# relay-set-d-decode.net
KiCad netlist of a schematic drawn in EAGLE
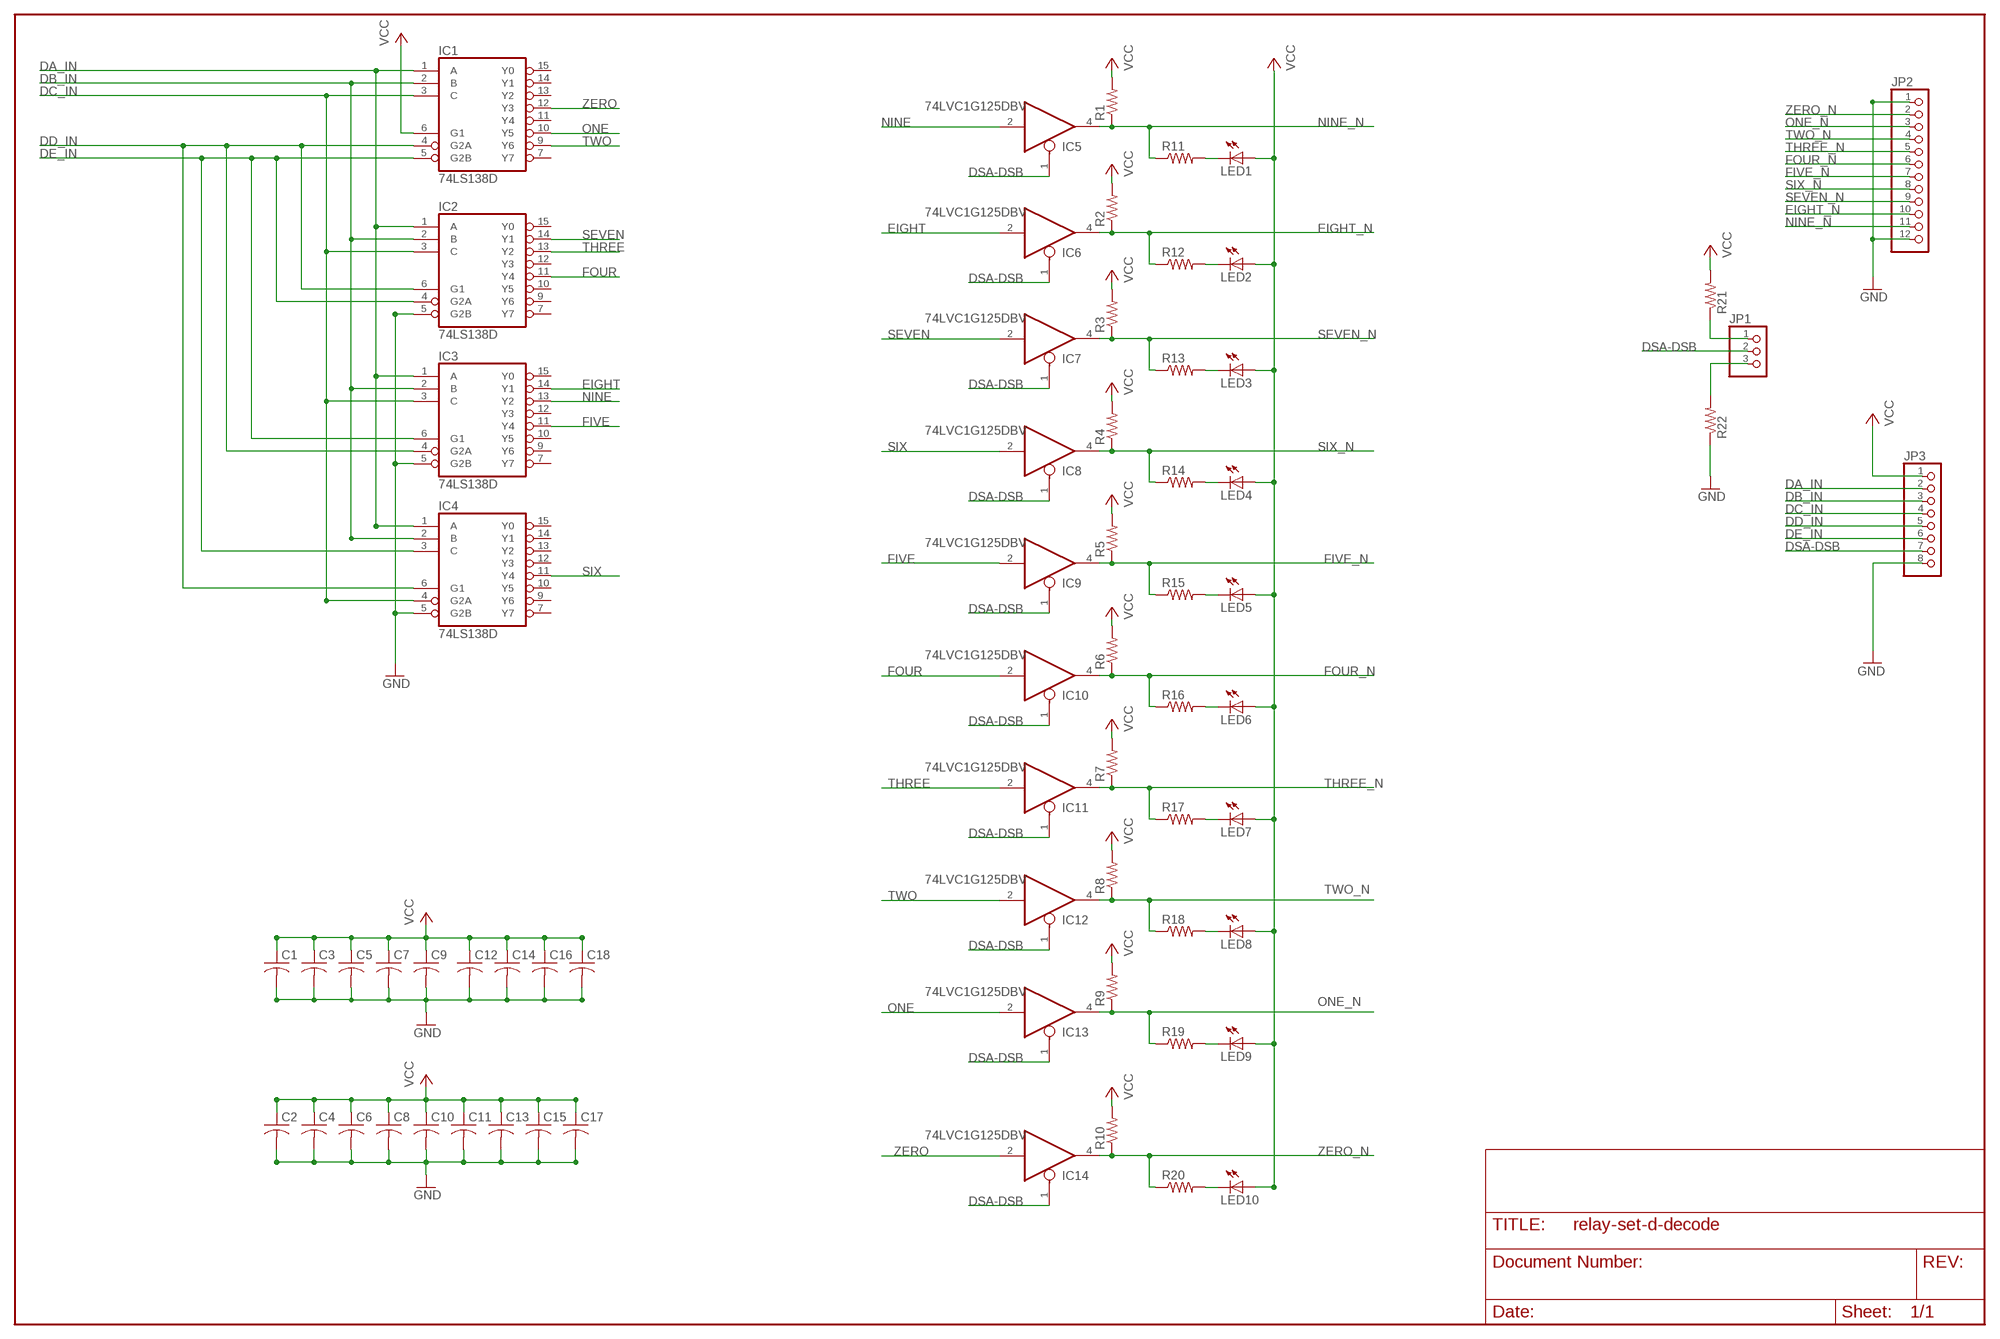
[diagram p0: schematic, sheet 1]

(export (version "E")
  (design (tool "Eeschema 10.0.6"))
  (components
    (comp (ref "C1")
      (value "C-USC0603")
      (footprint "eagle-import:C0603")
      (libsource (lib "eagle-import") (part "C-USC0603"))
    )
    (comp (ref "C2")
      (value "C-USC0603")
      (footprint "eagle-import:C0603")
      (libsource (lib "eagle-import") (part "C-USC0603"))
    )
    (comp (ref "C3")
      (value "C-USC0603")
      (footprint "eagle-import:C0603")
      (libsource (lib "eagle-import") (part "C-USC0603"))
    )
    (comp (ref "C4")
      (value "C-USC0603")
      (footprint "eagle-import:C0603")
      (libsource (lib "eagle-import") (part "C-USC0603"))
    )
    (comp (ref "C5")
      (value "C-USC0805")
      (footprint "eagle-import:C0805")
      (libsource (lib "eagle-import") (part "C-USC0805"))
    )
    (comp (ref "C6")
      (value "C-USC0603")
      (footprint "eagle-import:C0603")
      (libsource (lib "eagle-import") (part "C-USC0603"))
    )
    (comp (ref "C7")
      (value "C-USC0805")
      (footprint "eagle-import:C0805")
      (libsource (lib "eagle-import") (part "C-USC0805"))
    )
    (comp (ref "C8")
      (value "C-USC0603")
      (footprint "eagle-import:C0603")
      (libsource (lib "eagle-import") (part "C-USC0603"))
    )
    (comp (ref "C9")
      (value "C-USC0805")
      (footprint "eagle-import:C0805")
      (libsource (lib "eagle-import") (part "C-USC0805"))
    )
    (comp (ref "C10")
      (value "C-USC0603")
      (footprint "eagle-import:C0603")
      (libsource (lib "eagle-import") (part "C-USC0603"))
    )
    (comp (ref "C11")
      (value "C-USC0603")
      (footprint "eagle-import:C0603")
      (libsource (lib "eagle-import") (part "C-USC0603"))
    )
    (comp (ref "C12")
      (value "C-USC0603")
      (footprint "eagle-import:C0603")
      (libsource (lib "eagle-import") (part "C-USC0603"))
    )
    (comp (ref "C13")
      (value "C-USC0603")
      (footprint "eagle-import:C0603")
      (libsource (lib "eagle-import") (part "C-USC0603"))
    )
    (comp (ref "C14")
      (value "C-USC0603")
      (footprint "eagle-import:C0603")
      (libsource (lib "eagle-import") (part "C-USC0603"))
    )
    (comp (ref "C15")
      (value "C-USC0603")
      (footprint "eagle-import:C0603")
      (libsource (lib "eagle-import") (part "C-USC0603"))
    )
    (comp (ref "C16")
      (value "C-USC0603")
      (footprint "eagle-import:C0603")
      (libsource (lib "eagle-import") (part "C-USC0603"))
    )
    (comp (ref "C17")
      (value "C-USC0603")
      (footprint "eagle-import:C0603")
      (libsource (lib "eagle-import") (part "C-USC0603"))
    )
    (comp (ref "C18")
      (value "C-USC0603")
      (footprint "eagle-import:C0603")
      (libsource (lib "eagle-import") (part "C-USC0603"))
    )
    (comp (ref "IC1")
      (value "74LS138D")
      (footprint "eagle-import:SO16")
      (libsource (lib "eagle-import") (part "74138DLS"))
    )
    (comp (ref "IC2")
      (value "74LS138D")
      (footprint "eagle-import:SO16")
      (libsource (lib "eagle-import") (part "74138DLS"))
    )
    (comp (ref "IC3")
      (value "74LS138D")
      (footprint "eagle-import:SO16")
      (libsource (lib "eagle-import") (part "74138DLS"))
    )
    (comp (ref "IC4")
      (value "74LS138D")
      (footprint "eagle-import:SO16")
      (libsource (lib "eagle-import") (part "74138DLS"))
    )
    (comp (ref "IC5")
      (value "74LVC1G125DBV")
      (footprint "eagle-import:SOT23-5")
      (libsource (lib "eagle-import") (part "741G125DBVLVC"))
    )
    (comp (ref "IC6")
      (value "74LVC1G125DBV")
      (footprint "eagle-import:SOT23-5")
      (libsource (lib "eagle-import") (part "741G125DBVLVC"))
    )
    (comp (ref "IC7")
      (value "74LVC1G125DBV")
      (footprint "eagle-import:SOT23-5")
      (libsource (lib "eagle-import") (part "741G125DBVLVC"))
    )
    (comp (ref "IC8")
      (value "74LVC1G125DBV")
      (footprint "eagle-import:SOT23-5")
      (libsource (lib "eagle-import") (part "741G125DBVLVC"))
    )
    (comp (ref "IC9")
      (value "74LVC1G125DBV")
      (footprint "eagle-import:SOT23-5")
      (libsource (lib "eagle-import") (part "741G125DBVLVC"))
    )
    (comp (ref "IC10")
      (value "74LVC1G125DBV")
      (footprint "eagle-import:SOT23-5")
      (libsource (lib "eagle-import") (part "741G125DBVLVC"))
    )
    (comp (ref "IC11")
      (value "74LVC1G125DBV")
      (footprint "eagle-import:SOT23-5")
      (libsource (lib "eagle-import") (part "741G125DBVLVC"))
    )
    (comp (ref "IC12")
      (value "74LVC1G125DBV")
      (footprint "eagle-import:SOT23-5")
      (libsource (lib "eagle-import") (part "741G125DBVLVC"))
    )
    (comp (ref "IC13")
      (value "74LVC1G125DBV")
      (footprint "eagle-import:SOT23-5")
      (libsource (lib "eagle-import") (part "741G125DBVLVC"))
    )
    (comp (ref "IC14")
      (value "74LVC1G125DBV")
      (footprint "eagle-import:SOT23-5")
      (libsource (lib "eagle-import") (part "741G125DBVLVC"))
    )
    (comp (ref "JP1")
      (value "PINHD-1X3")
      (footprint "eagle-import:1X03")
      (libsource (lib "eagle-import") (part "PINHD-1X3"))
    )
    (comp (ref "JP2")
      (value "PINHD-1X12")
      (footprint "eagle-import:1X12")
      (libsource (lib "eagle-import") (part "PINHD-1X12"))
    )
    (comp (ref "JP3")
      (value "PINHD-1X8")
      (footprint "eagle-import:1X08")
      (libsource (lib "eagle-import") (part "PINHD-1X8"))
    )
    (comp (ref "LED1")
      (value "LEDCHIP-LED0805")
      (footprint "eagle-import:CHIP-LED0805")
      (libsource (lib "eagle-import") (part "LEDCHIP-LED0805"))
    )
    (comp (ref "LED2")
      (value "LEDCHIP-LED0805")
      (footprint "eagle-import:CHIP-LED0805")
      (libsource (lib "eagle-import") (part "LEDCHIP-LED0805"))
    )
    (comp (ref "LED3")
      (value "LEDCHIP-LED0805")
      (footprint "eagle-import:CHIP-LED0805")
      (libsource (lib "eagle-import") (part "LEDCHIP-LED0805"))
    )
    (comp (ref "LED4")
      (value "LEDCHIP-LED0805")
      (footprint "eagle-import:CHIP-LED0805")
      (libsource (lib "eagle-import") (part "LEDCHIP-LED0805"))
    )
    (comp (ref "LED5")
      (value "LEDCHIP-LED0805")
      (footprint "eagle-import:CHIP-LED0805")
      (libsource (lib "eagle-import") (part "LEDCHIP-LED0805"))
    )
    (comp (ref "LED6")
      (value "LEDCHIP-LED0805")
      (footprint "eagle-import:CHIP-LED0805")
      (libsource (lib "eagle-import") (part "LEDCHIP-LED0805"))
    )
    (comp (ref "LED7")
      (value "LEDCHIP-LED0805")
      (footprint "eagle-import:CHIP-LED0805")
      (libsource (lib "eagle-import") (part "LEDCHIP-LED0805"))
    )
    (comp (ref "LED8")
      (value "LEDCHIP-LED0805")
      (footprint "eagle-import:CHIP-LED0805")
      (libsource (lib "eagle-import") (part "LEDCHIP-LED0805"))
    )
    (comp (ref "LED9")
      (value "LEDCHIP-LED0805")
      (footprint "eagle-import:CHIP-LED0805")
      (libsource (lib "eagle-import") (part "LEDCHIP-LED0805"))
    )
    (comp (ref "LED10")
      (value "LEDCHIP-LED0805")
      (footprint "eagle-import:CHIP-LED0805")
      (libsource (lib "eagle-import") (part "LEDCHIP-LED0805"))
    )
    (comp (ref "R1")
      (value "R-US_R0805")
      (footprint "eagle-import:R0805")
      (libsource (lib "eagle-import") (part "R-US_R0805"))
    )
    (comp (ref "R2")
      (value "R-US_R0805")
      (footprint "eagle-import:R0805")
      (libsource (lib "eagle-import") (part "R-US_R0805"))
    )
    (comp (ref "R3")
      (value "R-US_R0805")
      (footprint "eagle-import:R0805")
      (libsource (lib "eagle-import") (part "R-US_R0805"))
    )
    (comp (ref "R4")
      (value "R-US_R0805")
      (footprint "eagle-import:R0805")
      (libsource (lib "eagle-import") (part "R-US_R0805"))
    )
    (comp (ref "R5")
      (value "R-US_R0805")
      (footprint "eagle-import:R0805")
      (libsource (lib "eagle-import") (part "R-US_R0805"))
    )
    (comp (ref "R6")
      (value "R-US_R0805")
      (footprint "eagle-import:R0805")
      (libsource (lib "eagle-import") (part "R-US_R0805"))
    )
    (comp (ref "R7")
      (value "R-US_R0805")
      (footprint "eagle-import:R0805")
      (libsource (lib "eagle-import") (part "R-US_R0805"))
    )
    (comp (ref "R8")
      (value "R-US_R0805")
      (footprint "eagle-import:R0805")
      (libsource (lib "eagle-import") (part "R-US_R0805"))
    )
    (comp (ref "R9")
      (value "R-US_R0805")
      (footprint "eagle-import:R0805")
      (libsource (lib "eagle-import") (part "R-US_R0805"))
    )
    (comp (ref "R10")
      (value "R-US_R0805")
      (footprint "eagle-import:R0805")
      (libsource (lib "eagle-import") (part "R-US_R0805"))
    )
    (comp (ref "R11")
      (value "R-US_R0805")
      (footprint "eagle-import:R0805")
      (libsource (lib "eagle-import") (part "R-US_R0805"))
    )
    (comp (ref "R12")
      (value "R-US_R0805")
      (footprint "eagle-import:R0805")
      (libsource (lib "eagle-import") (part "R-US_R0805"))
    )
    (comp (ref "R13")
      (value "R-US_R0805")
      (footprint "eagle-import:R0805")
      (libsource (lib "eagle-import") (part "R-US_R0805"))
    )
    (comp (ref "R14")
      (value "R-US_R0805")
      (footprint "eagle-import:R0805")
      (libsource (lib "eagle-import") (part "R-US_R0805"))
    )
    (comp (ref "R15")
      (value "R-US_R0805")
      (footprint "eagle-import:R0805")
      (libsource (lib "eagle-import") (part "R-US_R0805"))
    )
    (comp (ref "R16")
      (value "R-US_R0805")
      (footprint "eagle-import:R0805")
      (libsource (lib "eagle-import") (part "R-US_R0805"))
    )
    (comp (ref "R17")
      (value "R-US_R0805")
      (footprint "eagle-import:R0805")
      (libsource (lib "eagle-import") (part "R-US_R0805"))
    )
    (comp (ref "R18")
      (value "R-US_R0805")
      (footprint "eagle-import:R0805")
      (libsource (lib "eagle-import") (part "R-US_R0805"))
    )
    (comp (ref "R19")
      (value "R-US_R0805")
      (footprint "eagle-import:R0805")
      (libsource (lib "eagle-import") (part "R-US_R0805"))
    )
    (comp (ref "R20")
      (value "R-US_R0805")
      (footprint "eagle-import:R0805")
      (libsource (lib "eagle-import") (part "R-US_R0805"))
    )
    (comp (ref "R21")
      (value "R-US_R0805")
      (footprint "eagle-import:R0805")
      (libsource (lib "eagle-import") (part "R-US_R0805"))
    )
    (comp (ref "R22")
      (value "R-US_R0805")
      (footprint "eagle-import:R0805")
      (libsource (lib "eagle-import") (part "R-US_R0805"))
    )
  )
  (nets
    (net (code "1") (name "/DA_IN") (class "Default")
      (node (ref "IC1") (pin "1") (pinfunction "A_1") (pintype "input"))
      (node (ref "IC2") (pin "1") (pinfunction "A_1") (pintype "input"))
      (node (ref "IC3") (pin "1") (pinfunction "A_1") (pintype "input"))
      (node (ref "IC4") (pin "1") (pinfunction "A_1") (pintype "input"))
      (node (ref "JP3") (pin "2") (pinfunction "2_2") (pintype "passive"))
    )
    (net (code "2") (name "/DB_IN") (class "Default")
      (node (ref "IC1") (pin "2") (pinfunction "B_2") (pintype "input"))
      (node (ref "IC2") (pin "2") (pinfunction "B_2") (pintype "input"))
      (node (ref "IC3") (pin "2") (pinfunction "B_2") (pintype "input"))
      (node (ref "IC4") (pin "2") (pinfunction "B_2") (pintype "input"))
      (node (ref "JP3") (pin "3") (pinfunction "3_3") (pintype "passive"))
    )
    (net (code "3") (name "/DC_IN") (class "Default")
      (node (ref "IC1") (pin "3") (pinfunction "C_3") (pintype "input"))
      (node (ref "IC2") (pin "3") (pinfunction "C_3") (pintype "input"))
      (node (ref "IC3") (pin "3") (pinfunction "C_3") (pintype "input"))
      (node (ref "IC4") (pin "4") (pinfunction "G2A_4") (pintype "input"))
      (node (ref "JP3") (pin "4") (pinfunction "4_4") (pintype "passive"))
    )
    (net (code "4") (name "/DD_IN") (class "Default")
      (node (ref "IC1") (pin "4") (pinfunction "G2A_4") (pintype "input"))
      (node (ref "IC2") (pin "6") (pinfunction "G1_6") (pintype "input"))
      (node (ref "IC3") (pin "4") (pinfunction "G2A_4") (pintype "input"))
      (node (ref "IC4") (pin "6") (pinfunction "G1_6") (pintype "input"))
      (node (ref "JP3") (pin "5") (pinfunction "5_5") (pintype "passive"))
    )
    (net (code "5") (name "/DE_IN") (class "Default")
      (node (ref "IC1") (pin "5") (pinfunction "G2B_5") (pintype "input"))
      (node (ref "IC2") (pin "4") (pinfunction "G2A_4") (pintype "input"))
      (node (ref "IC3") (pin "6") (pinfunction "G1_6") (pintype "input"))
      (node (ref "IC4") (pin "3") (pinfunction "C_3") (pintype "input"))
      (node (ref "JP3") (pin "6") (pinfunction "6_6") (pintype "passive"))
    )
    (net (code "6") (name "/DSA-DSB") (class "Default")
      (node (ref "IC10") (pin "1") (pinfunction "OE_1") (pintype "input"))
      (node (ref "IC11") (pin "1") (pinfunction "OE_1") (pintype "input"))
      (node (ref "IC12") (pin "1") (pinfunction "OE_1") (pintype "input"))
      (node (ref "IC13") (pin "1") (pinfunction "OE_1") (pintype "input"))
      (node (ref "IC14") (pin "1") (pinfunction "OE_1") (pintype "input"))
      (node (ref "IC5") (pin "1") (pinfunction "OE_1") (pintype "input"))
      (node (ref "IC6") (pin "1") (pinfunction "OE_1") (pintype "input"))
      (node (ref "IC7") (pin "1") (pinfunction "OE_1") (pintype "input"))
      (node (ref "IC8") (pin "1") (pinfunction "OE_1") (pintype "input"))
      (node (ref "IC9") (pin "1") (pinfunction "OE_1") (pintype "input"))
      (node (ref "JP1") (pin "2") (pinfunction "2_2") (pintype "passive"))
      (node (ref "JP3") (pin "7") (pinfunction "7_7") (pintype "passive"))
    )
    (net (code "7") (name "/EIGHT") (class "Default")
      (node (ref "IC3") (pin "14") (pinfunction "Y1_14") (pintype "output"))
      (node (ref "IC6") (pin "2") (pinfunction "I_2") (pintype "input"))
    )
    (net (code "8") (name "/EIGHT_N") (class "Default")
      (node (ref "IC6") (pin "4") (pinfunction "O_4") (pintype "tri_state"))
      (node (ref "JP2") (pin "10") (pinfunction "10_10") (pintype "passive"))
      (node (ref "R12") (pin "1") (pinfunction "1_1") (pintype "passive"))
      (node (ref "R2") (pin "1") (pinfunction "1_1") (pintype "passive"))
    )
    (net (code "9") (name "/FIVE") (class "Default")
      (node (ref "IC3") (pin "11") (pinfunction "Y4_11") (pintype "output"))
      (node (ref "IC9") (pin "2") (pinfunction "I_2") (pintype "input"))
    )
    (net (code "10") (name "/FIVE_N") (class "Default")
      (node (ref "IC9") (pin "4") (pinfunction "O_4") (pintype "tri_state"))
      (node (ref "JP2") (pin "7") (pinfunction "7_7") (pintype "passive"))
      (node (ref "R15") (pin "1") (pinfunction "1_1") (pintype "passive"))
      (node (ref "R5") (pin "1") (pinfunction "1_1") (pintype "passive"))
    )
    (net (code "11") (name "/FOUR") (class "Default")
      (node (ref "IC10") (pin "2") (pinfunction "I_2") (pintype "input"))
      (node (ref "IC2") (pin "11") (pinfunction "Y4_11") (pintype "output"))
    )
    (net (code "12") (name "/FOUR_N") (class "Default")
      (node (ref "IC10") (pin "4") (pinfunction "O_4") (pintype "tri_state"))
      (node (ref "JP2") (pin "6") (pinfunction "6_6") (pintype "passive"))
      (node (ref "R16") (pin "1") (pinfunction "1_1") (pintype "passive"))
      (node (ref "R6") (pin "1") (pinfunction "1_1") (pintype "passive"))
    )
    (net (code "13") (name "/NINE") (class "Default")
      (node (ref "IC3") (pin "13") (pinfunction "Y2_13") (pintype "output"))
      (node (ref "IC5") (pin "2") (pinfunction "I_2") (pintype "input"))
    )
    (net (code "14") (name "/NINE_N") (class "Default")
      (node (ref "IC5") (pin "4") (pinfunction "O_4") (pintype "tri_state"))
      (node (ref "JP2") (pin "11") (pinfunction "11_11") (pintype "passive"))
      (node (ref "R1") (pin "1") (pinfunction "1_1") (pintype "passive"))
      (node (ref "R11") (pin "1") (pinfunction "1_1") (pintype "passive"))
    )
    (net (code "15") (name "/ONE") (class "Default")
      (node (ref "IC1") (pin "10") (pinfunction "Y5_10") (pintype "output"))
      (node (ref "IC13") (pin "2") (pinfunction "I_2") (pintype "input"))
    )
    (net (code "16") (name "/ONE_N") (class "Default")
      (node (ref "IC13") (pin "4") (pinfunction "O_4") (pintype "tri_state"))
      (node (ref "JP2") (pin "3") (pinfunction "3_3") (pintype "passive"))
      (node (ref "R19") (pin "1") (pinfunction "1_1") (pintype "passive"))
      (node (ref "R9") (pin "1") (pinfunction "1_1") (pintype "passive"))
    )
    (net (code "17") (name "/SEVEN") (class "Default")
      (node (ref "IC2") (pin "14") (pinfunction "Y1_14") (pintype "output"))
      (node (ref "IC7") (pin "2") (pinfunction "I_2") (pintype "input"))
    )
    (net (code "18") (name "/SEVEN_N") (class "Default")
      (node (ref "IC7") (pin "4") (pinfunction "O_4") (pintype "tri_state"))
      (node (ref "JP2") (pin "9") (pinfunction "9_9") (pintype "passive"))
      (node (ref "R13") (pin "1") (pinfunction "1_1") (pintype "passive"))
      (node (ref "R3") (pin "1") (pinfunction "1_1") (pintype "passive"))
    )
    (net (code "19") (name "/SIX") (class "Default")
      (node (ref "IC4") (pin "11") (pinfunction "Y4_11") (pintype "output"))
      (node (ref "IC8") (pin "2") (pinfunction "I_2") (pintype "input"))
    )
    (net (code "20") (name "/SIX_N") (class "Default")
      (node (ref "IC8") (pin "4") (pinfunction "O_4") (pintype "tri_state"))
      (node (ref "JP2") (pin "8") (pinfunction "8_8") (pintype "passive"))
      (node (ref "R14") (pin "1") (pinfunction "1_1") (pintype "passive"))
      (node (ref "R4") (pin "1") (pinfunction "1_1") (pintype "passive"))
    )
    (net (code "21") (name "/THREE") (class "Default")
      (node (ref "IC11") (pin "2") (pinfunction "I_2") (pintype "input"))
      (node (ref "IC2") (pin "13") (pinfunction "Y2_13") (pintype "output"))
    )
    (net (code "22") (name "/THREE_N") (class "Default")
      (node (ref "IC11") (pin "4") (pinfunction "O_4") (pintype "tri_state"))
      (node (ref "JP2") (pin "5") (pinfunction "5_5") (pintype "passive"))
      (node (ref "R17") (pin "1") (pinfunction "1_1") (pintype "passive"))
      (node (ref "R7") (pin "1") (pinfunction "1_1") (pintype "passive"))
    )
    (net (code "23") (name "/TWO") (class "Default")
      (node (ref "IC1") (pin "9") (pinfunction "Y6_9") (pintype "output"))
      (node (ref "IC12") (pin "2") (pinfunction "I_2") (pintype "input"))
    )
    (net (code "24") (name "/TWO_N") (class "Default")
      (node (ref "IC12") (pin "4") (pinfunction "O_4") (pintype "tri_state"))
      (node (ref "JP2") (pin "4") (pinfunction "4_4") (pintype "passive"))
      (node (ref "R18") (pin "1") (pinfunction "1_1") (pintype "passive"))
      (node (ref "R8") (pin "1") (pinfunction "1_1") (pintype "passive"))
    )
    (net (code "25") (name "/ZERO") (class "Default")
      (node (ref "IC1") (pin "12") (pinfunction "Y3_12") (pintype "output"))
      (node (ref "IC14") (pin "2") (pinfunction "I_2") (pintype "input"))
    )
    (net (code "26") (name "/ZERO_N") (class "Default")
      (node (ref "IC14") (pin "4") (pinfunction "O_4") (pintype "tri_state"))
      (node (ref "JP2") (pin "2") (pinfunction "2_2") (pintype "passive"))
      (node (ref "R10") (pin "1") (pinfunction "1_1") (pintype "passive"))
      (node (ref "R20") (pin "1") (pinfunction "1_1") (pintype "passive"))
    )
    (net (code "27") (name "GND") (class "Default")
      (node (ref "C1") (pin "2") (pinfunction "2_2") (pintype "passive"))
      (node (ref "C10") (pin "2") (pinfunction "2_2") (pintype "passive"))
      (node (ref "C11") (pin "2") (pinfunction "2_2") (pintype "passive"))
      (node (ref "C12") (pin "2") (pinfunction "2_2") (pintype "passive"))
      (node (ref "C13") (pin "2") (pinfunction "2_2") (pintype "passive"))
      (node (ref "C14") (pin "2") (pinfunction "2_2") (pintype "passive"))
      (node (ref "C15") (pin "2") (pinfunction "2_2") (pintype "passive"))
      (node (ref "C16") (pin "2") (pinfunction "2_2") (pintype "passive"))
      (node (ref "C17") (pin "2") (pinfunction "2_2") (pintype "passive"))
      (node (ref "C18") (pin "2") (pinfunction "2_2") (pintype "passive"))
      (node (ref "C2") (pin "2") (pinfunction "2_2") (pintype "passive"))
      (node (ref "C3") (pin "2") (pinfunction "2_2") (pintype "passive"))
      (node (ref "C4") (pin "2") (pinfunction "2_2") (pintype "passive"))
      (node (ref "C5") (pin "2") (pinfunction "2_2") (pintype "passive"))
      (node (ref "C6") (pin "2") (pinfunction "2_2") (pintype "passive"))
      (node (ref "C7") (pin "2") (pinfunction "2_2") (pintype "passive"))
      (node (ref "C8") (pin "2") (pinfunction "2_2") (pintype "passive"))
      (node (ref "C9") (pin "2") (pinfunction "2_2") (pintype "passive"))
      (node (ref "IC2") (pin "5") (pinfunction "G2B_5") (pintype "input"))
      (node (ref "IC3") (pin "5") (pinfunction "G2B_5") (pintype "input"))
      (node (ref "IC4") (pin "5") (pinfunction "G2B_5") (pintype "input"))
      (node (ref "JP2") (pin "1") (pinfunction "1_1") (pintype "passive"))
      (node (ref "JP2") (pin "12") (pinfunction "12_12") (pintype "passive"))
      (node (ref "JP3") (pin "8") (pinfunction "8_8") (pintype "passive"))
      (node (ref "R22") (pin "1") (pinfunction "1_1") (pintype "passive"))
    )
    (net (code "28") (name "Net-(JP1-Pad1)") (class "Default")
      (node (ref "JP1") (pin "1") (pinfunction "1_1") (pintype "passive"))
      (node (ref "R21") (pin "1") (pinfunction "1_1") (pintype "passive"))
    )
    (net (code "29") (name "Net-(JP1-Pad3)") (class "Default")
      (node (ref "JP1") (pin "3") (pinfunction "3_3") (pintype "passive"))
      (node (ref "R22") (pin "2") (pinfunction "2_2") (pintype "passive"))
    )
    (net (code "30") (name "Net-(LED1-PadC)") (class "Default")
      (node (ref "LED1") (pin "C") (pinfunction "C_C") (pintype "passive"))
      (node (ref "R11") (pin "2") (pinfunction "2_2") (pintype "passive"))
    )
    (net (code "31") (name "Net-(LED2-PadC)") (class "Default")
      (node (ref "LED2") (pin "C") (pinfunction "C_C") (pintype "passive"))
      (node (ref "R12") (pin "2") (pinfunction "2_2") (pintype "passive"))
    )
    (net (code "32") (name "Net-(LED3-PadC)") (class "Default")
      (node (ref "LED3") (pin "C") (pinfunction "C_C") (pintype "passive"))
      (node (ref "R13") (pin "2") (pinfunction "2_2") (pintype "passive"))
    )
    (net (code "33") (name "Net-(LED4-PadC)") (class "Default")
      (node (ref "LED4") (pin "C") (pinfunction "C_C") (pintype "passive"))
      (node (ref "R14") (pin "2") (pinfunction "2_2") (pintype "passive"))
    )
    (net (code "34") (name "Net-(LED5-PadC)") (class "Default")
      (node (ref "LED5") (pin "C") (pinfunction "C_C") (pintype "passive"))
      (node (ref "R15") (pin "2") (pinfunction "2_2") (pintype "passive"))
    )
    (net (code "35") (name "Net-(LED6-PadC)") (class "Default")
      (node (ref "LED6") (pin "C") (pinfunction "C_C") (pintype "passive"))
      (node (ref "R16") (pin "2") (pinfunction "2_2") (pintype "passive"))
    )
    (net (code "36") (name "Net-(LED7-PadC)") (class "Default")
      (node (ref "LED7") (pin "C") (pinfunction "C_C") (pintype "passive"))
      (node (ref "R17") (pin "2") (pinfunction "2_2") (pintype "passive"))
    )
    (net (code "37") (name "Net-(LED8-PadC)") (class "Default")
      (node (ref "LED8") (pin "C") (pinfunction "C_C") (pintype "passive"))
      (node (ref "R18") (pin "2") (pinfunction "2_2") (pintype "passive"))
    )
    (net (code "38") (name "Net-(LED9-PadC)") (class "Default")
      (node (ref "LED9") (pin "C") (pinfunction "C_C") (pintype "passive"))
      (node (ref "R19") (pin "2") (pinfunction "2_2") (pintype "passive"))
    )
    (net (code "39") (name "Net-(LED10-PadC)") (class "Default")
      (node (ref "LED10") (pin "C") (pinfunction "C_C") (pintype "passive"))
      (node (ref "R20") (pin "2") (pinfunction "2_2") (pintype "passive"))
    )
    (net (code "40") (name "VCC") (class "Default")
      (node (ref "C1") (pin "1") (pinfunction "1_1") (pintype "passive"))
      (node (ref "C10") (pin "1") (pinfunction "1_1") (pintype "passive"))
      (node (ref "C11") (pin "1") (pinfunction "1_1") (pintype "passive"))
      (node (ref "C12") (pin "1") (pinfunction "1_1") (pintype "passive"))
      (node (ref "C13") (pin "1") (pinfunction "1_1") (pintype "passive"))
      (node (ref "C14") (pin "1") (pinfunction "1_1") (pintype "passive"))
      (node (ref "C15") (pin "1") (pinfunction "1_1") (pintype "passive"))
      (node (ref "C16") (pin "1") (pinfunction "1_1") (pintype "passive"))
      (node (ref "C17") (pin "1") (pinfunction "1_1") (pintype "passive"))
      (node (ref "C18") (pin "1") (pinfunction "1_1") (pintype "passive"))
      (node (ref "C2") (pin "1") (pinfunction "1_1") (pintype "passive"))
      (node (ref "C3") (pin "1") (pinfunction "1_1") (pintype "passive"))
      (node (ref "C4") (pin "1") (pinfunction "1_1") (pintype "passive"))
      (node (ref "C5") (pin "1") (pinfunction "1_1") (pintype "passive"))
      (node (ref "C6") (pin "1") (pinfunction "1_1") (pintype "passive"))
      (node (ref "C7") (pin "1") (pinfunction "1_1") (pintype "passive"))
      (node (ref "C8") (pin "1") (pinfunction "1_1") (pintype "passive"))
      (node (ref "C9") (pin "1") (pinfunction "1_1") (pintype "passive"))
      (node (ref "IC1") (pin "6") (pinfunction "G1_6") (pintype "input"))
      (node (ref "JP3") (pin "1") (pinfunction "1_1") (pintype "passive"))
      (node (ref "LED1") (pin "A") (pinfunction "A_A") (pintype "passive"))
      (node (ref "LED10") (pin "A") (pinfunction "A_A") (pintype "passive"))
      (node (ref "LED2") (pin "A") (pinfunction "A_A") (pintype "passive"))
      (node (ref "LED3") (pin "A") (pinfunction "A_A") (pintype "passive"))
      (node (ref "LED4") (pin "A") (pinfunction "A_A") (pintype "passive"))
      (node (ref "LED5") (pin "A") (pinfunction "A_A") (pintype "passive"))
      (node (ref "LED6") (pin "A") (pinfunction "A_A") (pintype "passive"))
      (node (ref "LED7") (pin "A") (pinfunction "A_A") (pintype "passive"))
      (node (ref "LED8") (pin "A") (pinfunction "A_A") (pintype "passive"))
      (node (ref "LED9") (pin "A") (pinfunction "A_A") (pintype "passive"))
      (node (ref "R1") (pin "2") (pinfunction "2_2") (pintype "passive"))
      (node (ref "R10") (pin "2") (pinfunction "2_2") (pintype "passive"))
      (node (ref "R2") (pin "2") (pinfunction "2_2") (pintype "passive"))
      (node (ref "R21") (pin "2") (pinfunction "2_2") (pintype "passive"))
      (node (ref "R3") (pin "2") (pinfunction "2_2") (pintype "passive"))
      (node (ref "R4") (pin "2") (pinfunction "2_2") (pintype "passive"))
      (node (ref "R5") (pin "2") (pinfunction "2_2") (pintype "passive"))
      (node (ref "R6") (pin "2") (pinfunction "2_2") (pintype "passive"))
      (node (ref "R7") (pin "2") (pinfunction "2_2") (pintype "passive"))
      (node (ref "R8") (pin "2") (pinfunction "2_2") (pintype "passive"))
      (node (ref "R9") (pin "2") (pinfunction "2_2") (pintype "passive"))
    )
    (net (code "41") (name "unconnected-(IC1A-Y0-Pad15)") (class "Default")
      (node (ref "IC1") (pin "15") (pinfunction "Y0_15") (pintype "output"))
    )
    (net (code "42") (name "unconnected-(IC1A-Y1-Pad14)") (class "Default")
      (node (ref "IC1") (pin "14") (pinfunction "Y1_14") (pintype "output"))
    )
    (net (code "43") (name "unconnected-(IC1A-Y2-Pad13)") (class "Default")
      (node (ref "IC1") (pin "13") (pinfunction "Y2_13") (pintype "output"))
    )
    (net (code "44") (name "unconnected-(IC1A-Y4-Pad11)") (class "Default")
      (node (ref "IC1") (pin "11") (pinfunction "Y4_11") (pintype "output"))
    )
    (net (code "45") (name "unconnected-(IC1A-Y7-Pad7)") (class "Default")
      (node (ref "IC1") (pin "7") (pinfunction "Y7_7") (pintype "output"))
    )
    (net (code "46") (name "unconnected-(IC2A-Y0-Pad15)") (class "Default")
      (node (ref "IC2") (pin "15") (pinfunction "Y0_15") (pintype "output"))
    )
    (net (code "47") (name "unconnected-(IC2A-Y3-Pad12)") (class "Default")
      (node (ref "IC2") (pin "12") (pinfunction "Y3_12") (pintype "output"))
    )
    (net (code "48") (name "unconnected-(IC2A-Y5-Pad10)") (class "Default")
      (node (ref "IC2") (pin "10") (pinfunction "Y5_10") (pintype "output"))
    )
    (net (code "49") (name "unconnected-(IC2A-Y6-Pad9)") (class "Default")
      (node (ref "IC2") (pin "9") (pinfunction "Y6_9") (pintype "output"))
    )
    (net (code "50") (name "unconnected-(IC2A-Y7-Pad7)") (class "Default")
      (node (ref "IC2") (pin "7") (pinfunction "Y7_7") (pintype "output"))
    )
    (net (code "51") (name "unconnected-(IC3A-Y0-Pad15)") (class "Default")
      (node (ref "IC3") (pin "15") (pinfunction "Y0_15") (pintype "output"))
    )
    (net (code "52") (name "unconnected-(IC3A-Y3-Pad12)") (class "Default")
      (node (ref "IC3") (pin "12") (pinfunction "Y3_12") (pintype "output"))
    )
    (net (code "53") (name "unconnected-(IC3A-Y5-Pad10)") (class "Default")
      (node (ref "IC3") (pin "10") (pinfunction "Y5_10") (pintype "output"))
    )
    (net (code "54") (name "unconnected-(IC3A-Y6-Pad9)") (class "Default")
      (node (ref "IC3") (pin "9") (pinfunction "Y6_9") (pintype "output"))
    )
    (net (code "55") (name "unconnected-(IC3A-Y7-Pad7)") (class "Default")
      (node (ref "IC3") (pin "7") (pinfunction "Y7_7") (pintype "output"))
    )
    (net (code "56") (name "unconnected-(IC4A-Y0-Pad15)") (class "Default")
      (node (ref "IC4") (pin "15") (pinfunction "Y0_15") (pintype "output"))
    )
    (net (code "57") (name "unconnected-(IC4A-Y1-Pad14)") (class "Default")
      (node (ref "IC4") (pin "14") (pinfunction "Y1_14") (pintype "output"))
    )
    (net (code "58") (name "unconnected-(IC4A-Y2-Pad13)") (class "Default")
      (node (ref "IC4") (pin "13") (pinfunction "Y2_13") (pintype "output"))
    )
    (net (code "59") (name "unconnected-(IC4A-Y3-Pad12)") (class "Default")
      (node (ref "IC4") (pin "12") (pinfunction "Y3_12") (pintype "output"))
    )
    (net (code "60") (name "unconnected-(IC4A-Y5-Pad10)") (class "Default")
      (node (ref "IC4") (pin "10") (pinfunction "Y5_10") (pintype "output"))
    )
    (net (code "61") (name "unconnected-(IC4A-Y6-Pad9)") (class "Default")
      (node (ref "IC4") (pin "9") (pinfunction "Y6_9") (pintype "output"))
    )
    (net (code "62") (name "unconnected-(IC4A-Y7-Pad7)") (class "Default")
      (node (ref "IC4") (pin "7") (pinfunction "Y7_7") (pintype "output"))
    )
  )
)
